# LMS7002M_Power.net
KiCad netlist of a schematic drawn in Altium Designer
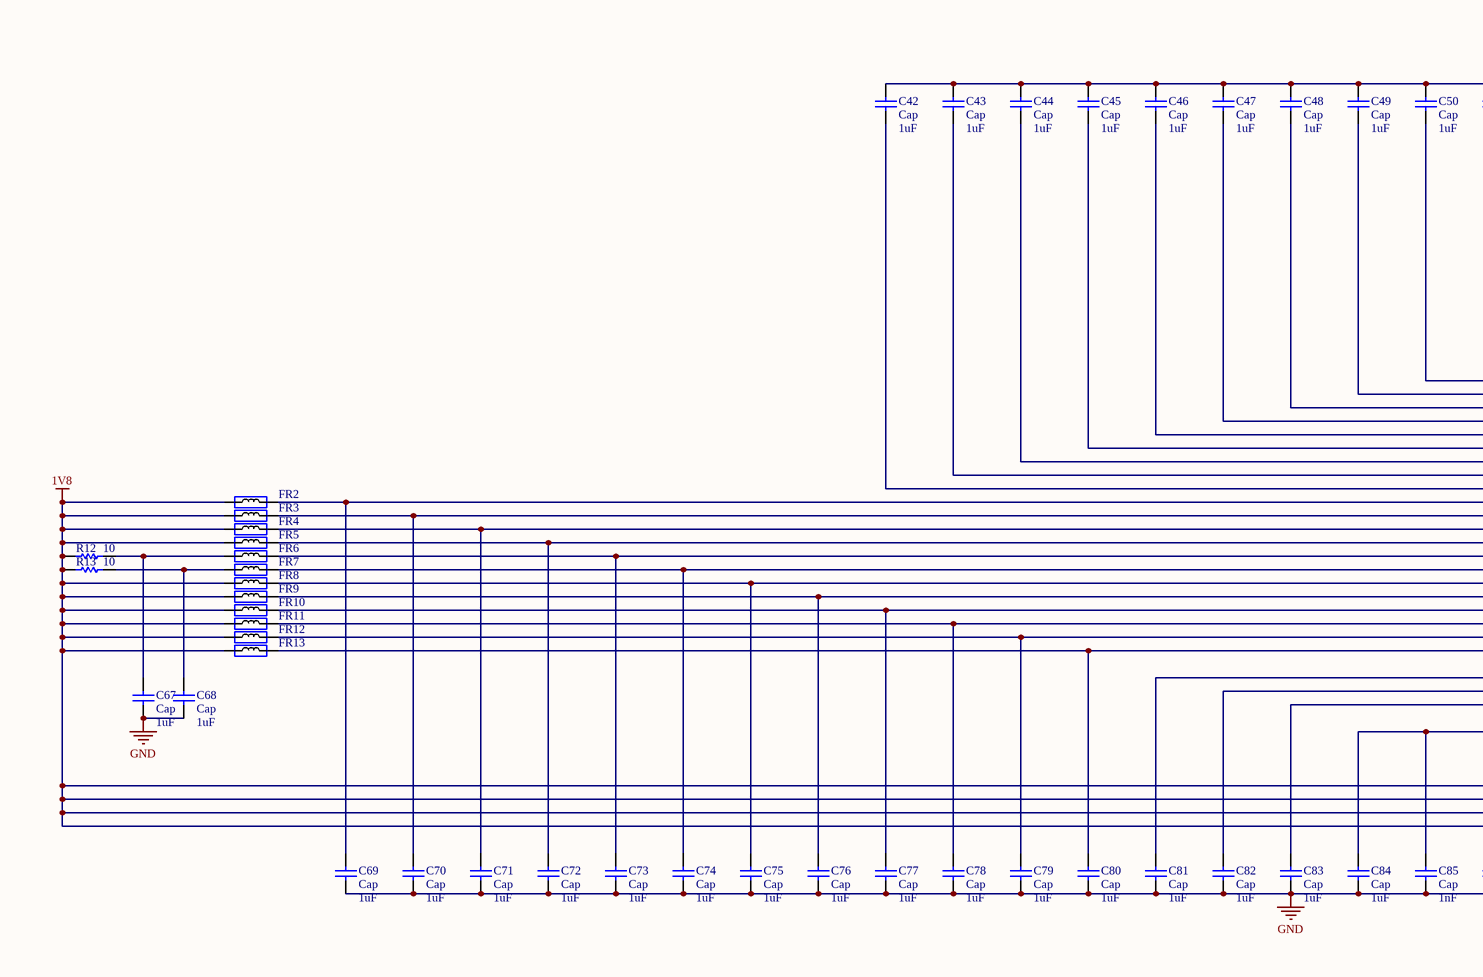
[diagram p0: LMS7002M Power.SchDoc, left]
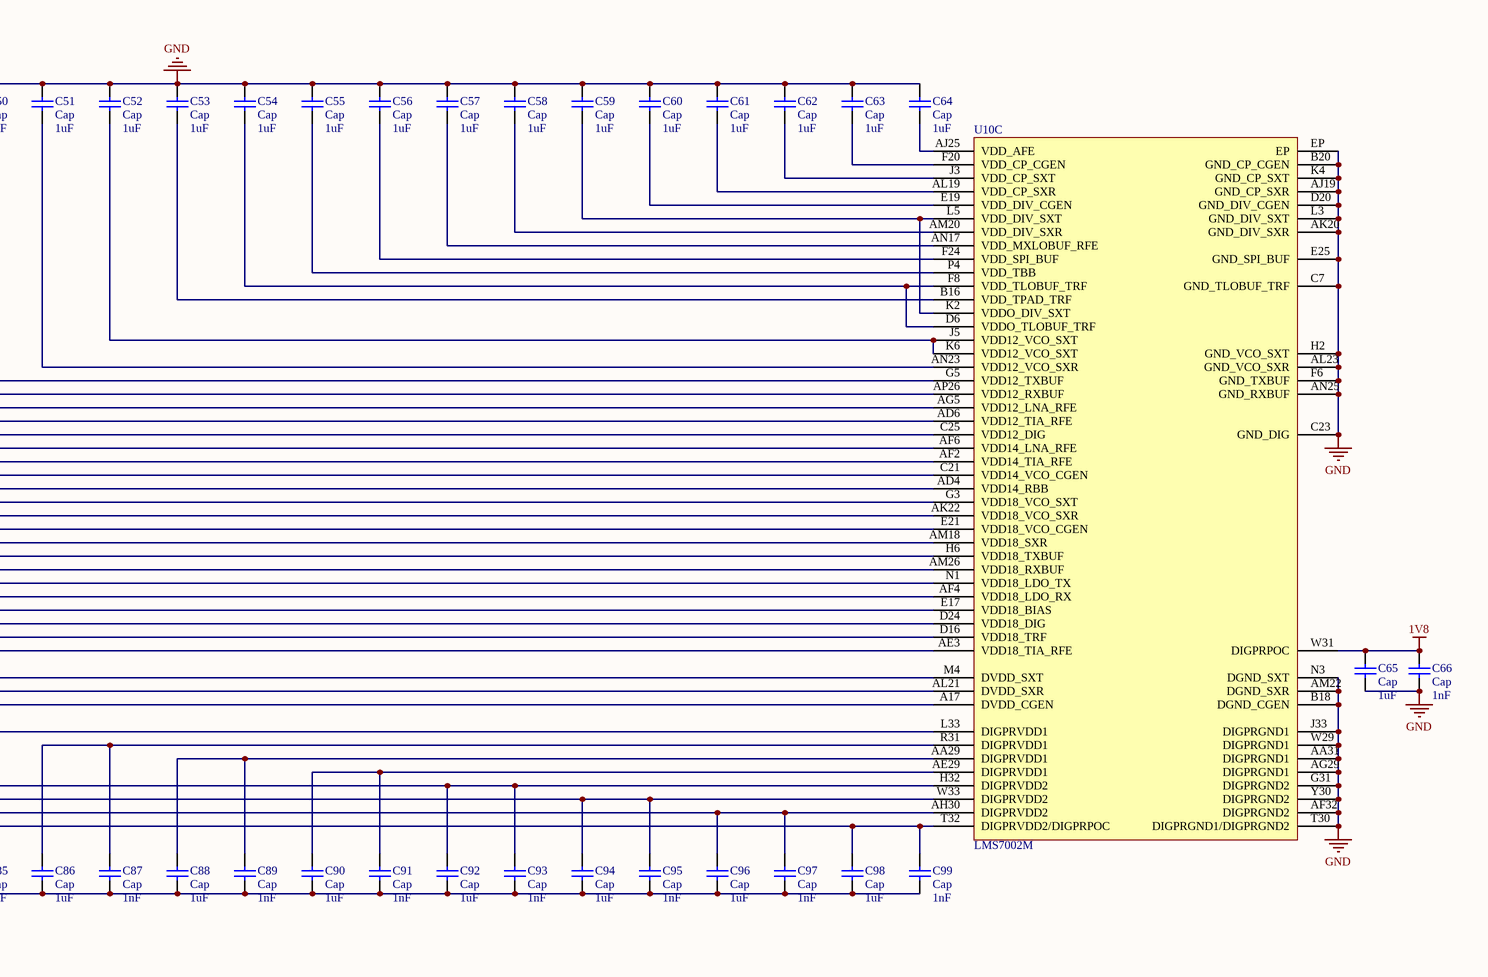
[diagram p1: LMS7002M Power.SchDoc, right]

(export (version "E")
  (design (tool "Eeschema 10.0.6"))
  (components
    (comp (ref "C42")
      (value "Cap")
      (footprint "0603")
      (description "Capacitor")
      (fields (field (name "ALTIUM_VALUE") "1uF") (field (name "PUBLISHER") "Altium Limited"))
      (libsource (lib "Miscellaneous Devices") (part "Cap"))
    )
    (comp (ref "C43")
      (value "Cap")
      (footprint "0603")
      (description "Capacitor")
      (fields (field (name "ALTIUM_VALUE") "1uF") (field (name "PUBLISHER") "Altium Limited"))
      (libsource (lib "Miscellaneous Devices") (part "Cap"))
    )
    (comp (ref "C44")
      (value "Cap")
      (footprint "0603")
      (description "Capacitor")
      (fields (field (name "ALTIUM_VALUE") "1uF") (field (name "PUBLISHER") "Altium Limited"))
      (libsource (lib "Miscellaneous Devices") (part "Cap"))
    )
    (comp (ref "C45")
      (value "Cap")
      (footprint "0603")
      (description "Capacitor")
      (fields (field (name "ALTIUM_VALUE") "1uF") (field (name "PUBLISHER") "Altium Limited"))
      (libsource (lib "Miscellaneous Devices") (part "Cap"))
    )
    (comp (ref "C46")
      (value "Cap")
      (footprint "0603")
      (description "Capacitor")
      (fields (field (name "ALTIUM_VALUE") "1uF") (field (name "PUBLISHER") "Altium Limited"))
      (libsource (lib "Miscellaneous Devices") (part "Cap"))
    )
    (comp (ref "C47")
      (value "Cap")
      (footprint "0603")
      (description "Capacitor")
      (fields (field (name "ALTIUM_VALUE") "1uF") (field (name "PUBLISHER") "Altium Limited"))
      (libsource (lib "Miscellaneous Devices") (part "Cap"))
    )
    (comp (ref "C48")
      (value "Cap")
      (footprint "0603")
      (description "Capacitor")
      (fields (field (name "ALTIUM_VALUE") "1uF") (field (name "PUBLISHER") "Altium Limited"))
      (libsource (lib "Miscellaneous Devices") (part "Cap"))
    )
    (comp (ref "C49")
      (value "Cap")
      (footprint "0603")
      (description "Capacitor")
      (fields (field (name "ALTIUM_VALUE") "1uF") (field (name "PUBLISHER") "Altium Limited"))
      (libsource (lib "Miscellaneous Devices") (part "Cap"))
    )
    (comp (ref "C50")
      (value "Cap")
      (footprint "0603")
      (description "Capacitor")
      (fields (field (name "ALTIUM_VALUE") "1uF") (field (name "PUBLISHER") "Altium Limited"))
      (libsource (lib "Miscellaneous Devices") (part "Cap"))
    )
    (comp (ref "C51")
      (value "Cap")
      (footprint "0603")
      (description "Capacitor")
      (fields (field (name "ALTIUM_VALUE") "1uF") (field (name "PUBLISHER") "Altium Limited"))
      (libsource (lib "Miscellaneous Devices") (part "Cap"))
    )
    (comp (ref "C52")
      (value "Cap")
      (footprint "0603")
      (description "Capacitor")
      (fields (field (name "ALTIUM_VALUE") "1uF") (field (name "PUBLISHER") "Altium Limited"))
      (libsource (lib "Miscellaneous Devices") (part "Cap"))
    )
    (comp (ref "C53")
      (value "Cap")
      (footprint "0603")
      (description "Capacitor")
      (fields (field (name "ALTIUM_VALUE") "1uF") (field (name "PUBLISHER") "Altium Limited"))
      (libsource (lib "Miscellaneous Devices") (part "Cap"))
    )
    (comp (ref "C54")
      (value "Cap")
      (footprint "0603")
      (description "Capacitor")
      (fields (field (name "ALTIUM_VALUE") "1uF") (field (name "PUBLISHER") "Altium Limited"))
      (libsource (lib "Miscellaneous Devices") (part "Cap"))
    )
    (comp (ref "C55")
      (value "Cap")
      (footprint "0603")
      (description "Capacitor")
      (fields (field (name "ALTIUM_VALUE") "1uF") (field (name "PUBLISHER") "Altium Limited"))
      (libsource (lib "Miscellaneous Devices") (part "Cap"))
    )
    (comp (ref "C56")
      (value "Cap")
      (footprint "0603")
      (description "Capacitor")
      (fields (field (name "ALTIUM_VALUE") "1uF") (field (name "PUBLISHER") "Altium Limited"))
      (libsource (lib "Miscellaneous Devices") (part "Cap"))
    )
    (comp (ref "C57")
      (value "Cap")
      (footprint "0603")
      (description "Capacitor")
      (fields (field (name "ALTIUM_VALUE") "1uF") (field (name "PUBLISHER") "Altium Limited"))
      (libsource (lib "Miscellaneous Devices") (part "Cap"))
    )
    (comp (ref "C58")
      (value "Cap")
      (footprint "0603")
      (description "Capacitor")
      (fields (field (name "ALTIUM_VALUE") "1uF") (field (name "PUBLISHER") "Altium Limited"))
      (libsource (lib "Miscellaneous Devices") (part "Cap"))
    )
    (comp (ref "C59")
      (value "Cap")
      (footprint "0603")
      (description "Capacitor")
      (fields (field (name "ALTIUM_VALUE") "1uF") (field (name "PUBLISHER") "Altium Limited"))
      (libsource (lib "Miscellaneous Devices") (part "Cap"))
    )
    (comp (ref "C60")
      (value "Cap")
      (footprint "0603")
      (description "Capacitor")
      (fields (field (name "ALTIUM_VALUE") "1uF") (field (name "PUBLISHER") "Altium Limited"))
      (libsource (lib "Miscellaneous Devices") (part "Cap"))
    )
    (comp (ref "C61")
      (value "Cap")
      (footprint "0603")
      (description "Capacitor")
      (fields (field (name "ALTIUM_VALUE") "1uF") (field (name "PUBLISHER") "Altium Limited"))
      (libsource (lib "Miscellaneous Devices") (part "Cap"))
    )
    (comp (ref "C62")
      (value "Cap")
      (footprint "0603")
      (description "Capacitor")
      (fields (field (name "ALTIUM_VALUE") "1uF") (field (name "PUBLISHER") "Altium Limited"))
      (libsource (lib "Miscellaneous Devices") (part "Cap"))
    )
    (comp (ref "C63")
      (value "Cap")
      (footprint "0603")
      (description "Capacitor")
      (fields (field (name "ALTIUM_VALUE") "1uF") (field (name "PUBLISHER") "Altium Limited"))
      (libsource (lib "Miscellaneous Devices") (part "Cap"))
    )
    (comp (ref "C64")
      (value "Cap")
      (footprint "0603")
      (description "Capacitor")
      (fields (field (name "ALTIUM_VALUE") "1uF") (field (name "PUBLISHER") "Altium Limited"))
      (libsource (lib "Miscellaneous Devices") (part "Cap"))
    )
    (comp (ref "C65")
      (value "Cap")
      (footprint "0603")
      (description "Capacitor")
      (fields (field (name "ALTIUM_VALUE") "1uF") (field (name "PUBLISHER") "Altium Limited"))
      (libsource (lib "Miscellaneous Devices") (part "Cap"))
    )
    (comp (ref "C66")
      (value "Cap")
      (footprint "0603")
      (description "Capacitor")
      (fields (field (name "ALTIUM_VALUE") "1nF") (field (name "PUBLISHER") "Altium Limited"))
      (libsource (lib "Miscellaneous Devices") (part "Cap"))
    )
    (comp (ref "C67")
      (value "Cap")
      (footprint "0603")
      (description "Capacitor")
      (fields (field (name "ALTIUM_VALUE") "1uF") (field (name "PUBLISHER") "Altium Limited"))
      (libsource (lib "Miscellaneous Devices") (part "Cap"))
    )
    (comp (ref "C68")
      (value "Cap")
      (footprint "0603")
      (description "Capacitor")
      (fields (field (name "ALTIUM_VALUE") "1uF") (field (name "PUBLISHER") "Altium Limited"))
      (libsource (lib "Miscellaneous Devices") (part "Cap"))
    )
    (comp (ref "C69")
      (value "Cap")
      (footprint "0603")
      (description "Capacitor")
      (fields (field (name "ALTIUM_VALUE") "1uF") (field (name "PUBLISHER") "Altium Limited"))
      (libsource (lib "Miscellaneous Devices") (part "Cap"))
    )
    (comp (ref "C70")
      (value "Cap")
      (footprint "0603")
      (description "Capacitor")
      (fields (field (name "ALTIUM_VALUE") "1uF") (field (name "PUBLISHER") "Altium Limited"))
      (libsource (lib "Miscellaneous Devices") (part "Cap"))
    )
    (comp (ref "C71")
      (value "Cap")
      (footprint "0603")
      (description "Capacitor")
      (fields (field (name "ALTIUM_VALUE") "1uF") (field (name "PUBLISHER") "Altium Limited"))
      (libsource (lib "Miscellaneous Devices") (part "Cap"))
    )
    (comp (ref "C72")
      (value "Cap")
      (footprint "0603")
      (description "Capacitor")
      (fields (field (name "ALTIUM_VALUE") "1uF") (field (name "PUBLISHER") "Altium Limited"))
      (libsource (lib "Miscellaneous Devices") (part "Cap"))
    )
    (comp (ref "C73")
      (value "Cap")
      (footprint "0603")
      (description "Capacitor")
      (fields (field (name "ALTIUM_VALUE") "1uF") (field (name "PUBLISHER") "Altium Limited"))
      (libsource (lib "Miscellaneous Devices") (part "Cap"))
    )
    (comp (ref "C74")
      (value "Cap")
      (footprint "0603")
      (description "Capacitor")
      (fields (field (name "ALTIUM_VALUE") "1uF") (field (name "PUBLISHER") "Altium Limited"))
      (libsource (lib "Miscellaneous Devices") (part "Cap"))
    )
    (comp (ref "C75")
      (value "Cap")
      (footprint "0603")
      (description "Capacitor")
      (fields (field (name "ALTIUM_VALUE") "1uF") (field (name "PUBLISHER") "Altium Limited"))
      (libsource (lib "Miscellaneous Devices") (part "Cap"))
    )
    (comp (ref "C76")
      (value "Cap")
      (footprint "0603")
      (description "Capacitor")
      (fields (field (name "ALTIUM_VALUE") "1uF") (field (name "PUBLISHER") "Altium Limited"))
      (libsource (lib "Miscellaneous Devices") (part "Cap"))
    )
    (comp (ref "C77")
      (value "Cap")
      (footprint "0603")
      (description "Capacitor")
      (fields (field (name "ALTIUM_VALUE") "1uF") (field (name "PUBLISHER") "Altium Limited"))
      (libsource (lib "Miscellaneous Devices") (part "Cap"))
    )
    (comp (ref "C78")
      (value "Cap")
      (footprint "0603")
      (description "Capacitor")
      (fields (field (name "ALTIUM_VALUE") "1uF") (field (name "PUBLISHER") "Altium Limited"))
      (libsource (lib "Miscellaneous Devices") (part "Cap"))
    )
    (comp (ref "C79")
      (value "Cap")
      (footprint "0603")
      (description "Capacitor")
      (fields (field (name "ALTIUM_VALUE") "1uF") (field (name "PUBLISHER") "Altium Limited"))
      (libsource (lib "Miscellaneous Devices") (part "Cap"))
    )
    (comp (ref "C80")
      (value "Cap")
      (footprint "0603")
      (description "Capacitor")
      (fields (field (name "ALTIUM_VALUE") "1uF") (field (name "PUBLISHER") "Altium Limited"))
      (libsource (lib "Miscellaneous Devices") (part "Cap"))
    )
    (comp (ref "C81")
      (value "Cap")
      (footprint "0603")
      (description "Capacitor")
      (fields (field (name "ALTIUM_VALUE") "1uF") (field (name "PUBLISHER") "Altium Limited"))
      (libsource (lib "Miscellaneous Devices") (part "Cap"))
    )
    (comp (ref "C82")
      (value "Cap")
      (footprint "0603")
      (description "Capacitor")
      (fields (field (name "ALTIUM_VALUE") "1uF") (field (name "PUBLISHER") "Altium Limited"))
      (libsource (lib "Miscellaneous Devices") (part "Cap"))
    )
    (comp (ref "C83")
      (value "Cap")
      (footprint "0603")
      (description "Capacitor")
      (fields (field (name "ALTIUM_VALUE") "1uF") (field (name "PUBLISHER") "Altium Limited"))
      (libsource (lib "Miscellaneous Devices") (part "Cap"))
    )
    (comp (ref "C84")
      (value "Cap")
      (footprint "0603")
      (description "Capacitor")
      (fields (field (name "ALTIUM_VALUE") "1uF") (field (name "PUBLISHER") "Altium Limited"))
      (libsource (lib "Miscellaneous Devices") (part "Cap"))
    )
    (comp (ref "C85")
      (value "Cap")
      (footprint "0603")
      (description "Capacitor")
      (fields (field (name "ALTIUM_VALUE") "1nF") (field (name "PUBLISHER") "Altium Limited"))
      (libsource (lib "Miscellaneous Devices") (part "Cap"))
    )
    (comp (ref "C86")
      (value "Cap")
      (footprint "0603")
      (description "Capacitor")
      (fields (field (name "ALTIUM_VALUE") "1uF") (field (name "PUBLISHER") "Altium Limited"))
      (libsource (lib "Miscellaneous Devices") (part "Cap"))
    )
    (comp (ref "C87")
      (value "Cap")
      (footprint "0603")
      (description "Capacitor")
      (fields (field (name "ALTIUM_VALUE") "1nF") (field (name "PUBLISHER") "Altium Limited"))
      (libsource (lib "Miscellaneous Devices") (part "Cap"))
    )
    (comp (ref "C88")
      (value "Cap")
      (footprint "0603")
      (description "Capacitor")
      (fields (field (name "ALTIUM_VALUE") "1uF") (field (name "PUBLISHER") "Altium Limited"))
      (libsource (lib "Miscellaneous Devices") (part "Cap"))
    )
    (comp (ref "C89")
      (value "Cap")
      (footprint "0603")
      (description "Capacitor")
      (fields (field (name "ALTIUM_VALUE") "1nF") (field (name "PUBLISHER") "Altium Limited"))
      (libsource (lib "Miscellaneous Devices") (part "Cap"))
    )
    (comp (ref "C90")
      (value "Cap")
      (footprint "0603")
      (description "Capacitor")
      (fields (field (name "ALTIUM_VALUE") "1uF") (field (name "PUBLISHER") "Altium Limited"))
      (libsource (lib "Miscellaneous Devices") (part "Cap"))
    )
    (comp (ref "C91")
      (value "Cap")
      (footprint "0603")
      (description "Capacitor")
      (fields (field (name "ALTIUM_VALUE") "1nF") (field (name "PUBLISHER") "Altium Limited"))
      (libsource (lib "Miscellaneous Devices") (part "Cap"))
    )
    (comp (ref "C92")
      (value "Cap")
      (footprint "0603")
      (description "Capacitor")
      (fields (field (name "ALTIUM_VALUE") "1uF") (field (name "PUBLISHER") "Altium Limited"))
      (libsource (lib "Miscellaneous Devices") (part "Cap"))
    )
    (comp (ref "C93")
      (value "Cap")
      (footprint "0603")
      (description "Capacitor")
      (fields (field (name "ALTIUM_VALUE") "1nF") (field (name "PUBLISHER") "Altium Limited"))
      (libsource (lib "Miscellaneous Devices") (part "Cap"))
    )
    (comp (ref "C94")
      (value "Cap")
      (footprint "0603")
      (description "Capacitor")
      (fields (field (name "ALTIUM_VALUE") "1uF") (field (name "PUBLISHER") "Altium Limited"))
      (libsource (lib "Miscellaneous Devices") (part "Cap"))
    )
    (comp (ref "C95")
      (value "Cap")
      (footprint "0603")
      (description "Capacitor")
      (fields (field (name "ALTIUM_VALUE") "1nF") (field (name "PUBLISHER") "Altium Limited"))
      (libsource (lib "Miscellaneous Devices") (part "Cap"))
    )
    (comp (ref "C96")
      (value "Cap")
      (footprint "0603")
      (description "Capacitor")
      (fields (field (name "ALTIUM_VALUE") "1uF") (field (name "PUBLISHER") "Altium Limited"))
      (libsource (lib "Miscellaneous Devices") (part "Cap"))
    )
    (comp (ref "C97")
      (value "Cap")
      (footprint "0603")
      (description "Capacitor")
      (fields (field (name "ALTIUM_VALUE") "1nF") (field (name "PUBLISHER") "Altium Limited"))
      (libsource (lib "Miscellaneous Devices") (part "Cap"))
    )
    (comp (ref "C98")
      (value "Cap")
      (footprint "0603")
      (description "Capacitor")
      (fields (field (name "ALTIUM_VALUE") "1uF") (field (name "PUBLISHER") "Altium Limited"))
      (libsource (lib "Miscellaneous Devices") (part "Cap"))
    )
    (comp (ref "C99")
      (value "Cap")
      (footprint "0603")
      (description "Capacitor")
      (fields (field (name "ALTIUM_VALUE") "1nF") (field (name "PUBLISHER") "Altium Limited"))
      (libsource (lib "Miscellaneous Devices") (part "Cap"))
    )
    (comp (ref "FR2")
      (value "600R, 0.27A")
      (footprint "0603")
      (fields (field (name "MANUFACTURER") "Taiyo Yuden"))
      (libsource (lib "LimeMicroAltiumLib_schLib") (part "Ferrite"))
    )
    (comp (ref "FR3")
      (value "600R, 0.27A")
      (footprint "0603")
      (fields (field (name "MANUFACTURER") "Taiyo Yuden"))
      (libsource (lib "LimeMicroAltiumLib_schLib") (part "Ferrite"))
    )
    (comp (ref "FR4")
      (value "600R, 0.27A")
      (footprint "0603")
      (fields (field (name "MANUFACTURER") "Taiyo Yuden"))
      (libsource (lib "LimeMicroAltiumLib_schLib") (part "Ferrite"))
    )
    (comp (ref "FR5")
      (value "600R, 0.27A")
      (footprint "0603")
      (fields (field (name "MANUFACTURER") "Taiyo Yuden"))
      (libsource (lib "LimeMicroAltiumLib_schLib") (part "Ferrite"))
    )
    (comp (ref "FR6")
      (value "600R, 0.27A")
      (footprint "0603")
      (fields (field (name "MANUFACTURER") "Taiyo Yuden"))
      (libsource (lib "LimeMicroAltiumLib_schLib") (part "Ferrite"))
    )
    (comp (ref "FR7")
      (value "600R, 0.27A")
      (footprint "0603")
      (fields (field (name "MANUFACTURER") "Taiyo Yuden"))
      (libsource (lib "LimeMicroAltiumLib_schLib") (part "Ferrite"))
    )
    (comp (ref "FR8")
      (value "600R, 0.27A")
      (footprint "0603")
      (fields (field (name "MANUFACTURER") "Taiyo Yuden"))
      (libsource (lib "LimeMicroAltiumLib_schLib") (part "Ferrite"))
    )
    (comp (ref "FR9")
      (value "600R, 0.27A")
      (footprint "0603")
      (fields (field (name "MANUFACTURER") "Taiyo Yuden"))
      (libsource (lib "LimeMicroAltiumLib_schLib") (part "Ferrite"))
    )
    (comp (ref "FR10")
      (value "600R, 0.27A")
      (footprint "0603")
      (fields (field (name "MANUFACTURER") "Taiyo Yuden"))
      (libsource (lib "LimeMicroAltiumLib_schLib") (part "Ferrite"))
    )
    (comp (ref "FR11")
      (value "600R, 0.27A")
      (footprint "0603")
      (fields (field (name "MANUFACTURER") "Taiyo Yuden"))
      (libsource (lib "LimeMicroAltiumLib_schLib") (part "Ferrite"))
    )
    (comp (ref "FR12")
      (value "600R, 0.27A")
      (footprint "0603")
      (fields (field (name "MANUFACTURER") "Taiyo Yuden"))
      (libsource (lib "LimeMicroAltiumLib_schLib") (part "Ferrite"))
    )
    (comp (ref "FR13")
      (value "600R, 0.27A")
      (footprint "0603")
      (fields (field (name "MANUFACTURER") "Taiyo Yuden"))
      (libsource (lib "LimeMicroAltiumLib_schLib") (part "Ferrite"))
    )
    (comp (ref "R12")
      (value "10")
      (footprint "0402-A")
      (description "Resistor")
      (fields (field (name "Comment") "Res1") (field (name "PUBLISHER") "Altium Limited"))
      (libsource (lib "Miscellaneous Devices") (part "Res1"))
    )
    (comp (ref "R13")
      (value "10")
      (footprint "0402-A")
      (description "Resistor")
      (fields (field (name "Comment") "Res1") (field (name "PUBLISHER") "Altium Limited"))
      (libsource (lib "Miscellaneous Devices") (part "Res1"))
    )
    (comp (ref "U10")
      (value "LMS7002M")
      (footprint "LM-QFN-261_V")
      (fields (field (name "MANUFACTURER") "LimeMicrosystemsLtd"))
      (libsource (lib "Altium Content Vault") (part "LM-LMS7002M-QFN-261"))
    )
  )
  (nets
    (net (code "1") (name "1V8") (class "Default")
      (node (ref "C65") (pin "2") (pinfunction "2_2") (pintype "passive"))
      (node (ref "C66") (pin "2") (pinfunction "2_2") (pintype "passive"))
      (node (ref "C92") (pin "2") (pinfunction "2_2") (pintype "passive"))
      (node (ref "C93") (pin "2") (pinfunction "2_2") (pintype "passive"))
      (node (ref "C94") (pin "2") (pinfunction "2_2") (pintype "passive"))
      (node (ref "C95") (pin "2") (pinfunction "2_2") (pintype "passive"))
      (node (ref "C96") (pin "2") (pinfunction "2_2") (pintype "passive"))
      (node (ref "C97") (pin "2") (pinfunction "2_2") (pintype "passive"))
      (node (ref "C98") (pin "2") (pinfunction "2_2") (pintype "passive"))
      (node (ref "C99") (pin "2") (pinfunction "2_2") (pintype "passive"))
      (node (ref "FR10") (pin "1") (pinfunction "1_1") (pintype "passive"))
      (node (ref "FR11") (pin "1") (pinfunction "1_1") (pintype "passive"))
      (node (ref "FR12") (pin "1") (pinfunction "1_1") (pintype "passive"))
      (node (ref "FR13") (pin "1") (pinfunction "1_1") (pintype "passive"))
      (node (ref "FR2") (pin "1") (pinfunction "1_1") (pintype "passive"))
      (node (ref "FR3") (pin "1") (pinfunction "1_1") (pintype "passive"))
      (node (ref "FR4") (pin "1") (pinfunction "1_1") (pintype "passive"))
      (node (ref "FR5") (pin "1") (pinfunction "1_1") (pintype "passive"))
      (node (ref "FR8") (pin "1") (pinfunction "1_1") (pintype "passive"))
      (node (ref "FR9") (pin "1") (pinfunction "1_1") (pintype "passive"))
      (node (ref "R12") (pin "1") (pinfunction "1_1") (pintype "passive"))
      (node (ref "R13") (pin "1") (pinfunction "1_1") (pintype "passive"))
      (node (ref "U10") (pin "AH30") (pinfunction "DIGPRVDD2_AH30") (pintype "power_in"))
      (node (ref "U10") (pin "H32") (pinfunction "DIGPRVDD2_H32") (pintype "power_in"))
      (node (ref "U10") (pin "T32") (pinfunction "DIGPRVDD2/DIGPRPOC_T32") (pintype "power_in"))
      (node (ref "U10") (pin "W31") (pinfunction "DIGPRPOC_W31") (pintype "passive"))
      (node (ref "U10") (pin "W33") (pinfunction "DIGPRVDD2_W33") (pintype "power_in"))
    )
    (net (code "2") (name "GND") (class "Default")
      (node (ref "C42") (pin "2") (pinfunction "2_2") (pintype "passive"))
      (node (ref "C43") (pin "2") (pinfunction "2_2") (pintype "passive"))
      (node (ref "C44") (pin "2") (pinfunction "2_2") (pintype "passive"))
      (node (ref "C45") (pin "2") (pinfunction "2_2") (pintype "passive"))
      (node (ref "C46") (pin "2") (pinfunction "2_2") (pintype "passive"))
      (node (ref "C47") (pin "2") (pinfunction "2_2") (pintype "passive"))
      (node (ref "C48") (pin "2") (pinfunction "2_2") (pintype "passive"))
      (node (ref "C49") (pin "2") (pinfunction "2_2") (pintype "passive"))
      (node (ref "C50") (pin "2") (pinfunction "2_2") (pintype "passive"))
      (node (ref "C51") (pin "2") (pinfunction "2_2") (pintype "passive"))
      (node (ref "C52") (pin "2") (pinfunction "2_2") (pintype "passive"))
      (node (ref "C53") (pin "2") (pinfunction "2_2") (pintype "passive"))
      (node (ref "C54") (pin "2") (pinfunction "2_2") (pintype "passive"))
      (node (ref "C55") (pin "2") (pinfunction "2_2") (pintype "passive"))
      (node (ref "C56") (pin "2") (pinfunction "2_2") (pintype "passive"))
      (node (ref "C57") (pin "2") (pinfunction "2_2") (pintype "passive"))
      (node (ref "C58") (pin "2") (pinfunction "2_2") (pintype "passive"))
      (node (ref "C59") (pin "2") (pinfunction "2_2") (pintype "passive"))
      (node (ref "C60") (pin "2") (pinfunction "2_2") (pintype "passive"))
      (node (ref "C61") (pin "2") (pinfunction "2_2") (pintype "passive"))
      (node (ref "C62") (pin "2") (pinfunction "2_2") (pintype "passive"))
      (node (ref "C63") (pin "2") (pinfunction "2_2") (pintype "passive"))
      (node (ref "C64") (pin "2") (pinfunction "2_2") (pintype "passive"))
      (node (ref "C65") (pin "1") (pinfunction "1_1") (pintype "passive"))
      (node (ref "C66") (pin "1") (pinfunction "1_1") (pintype "passive"))
      (node (ref "C67") (pin "1") (pinfunction "1_1") (pintype "passive"))
      (node (ref "C68") (pin "1") (pinfunction "1_1") (pintype "passive"))
      (node (ref "C69") (pin "1") (pinfunction "1_1") (pintype "passive"))
      (node (ref "C70") (pin "1") (pinfunction "1_1") (pintype "passive"))
      (node (ref "C71") (pin "1") (pinfunction "1_1") (pintype "passive"))
      (node (ref "C72") (pin "1") (pinfunction "1_1") (pintype "passive"))
      (node (ref "C73") (pin "1") (pinfunction "1_1") (pintype "passive"))
      (node (ref "C74") (pin "1") (pinfunction "1_1") (pintype "passive"))
      (node (ref "C75") (pin "1") (pinfunction "1_1") (pintype "passive"))
      (node (ref "C76") (pin "1") (pinfunction "1_1") (pintype "passive"))
      (node (ref "C77") (pin "1") (pinfunction "1_1") (pintype "passive"))
      (node (ref "C78") (pin "1") (pinfunction "1_1") (pintype "passive"))
      (node (ref "C79") (pin "1") (pinfunction "1_1") (pintype "passive"))
      (node (ref "C80") (pin "1") (pinfunction "1_1") (pintype "passive"))
      (node (ref "C81") (pin "1") (pinfunction "1_1") (pintype "passive"))
      (node (ref "C82") (pin "1") (pinfunction "1_1") (pintype "passive"))
      (node (ref "C83") (pin "1") (pinfunction "1_1") (pintype "passive"))
      (node (ref "C84") (pin "1") (pinfunction "1_1") (pintype "passive"))
      (node (ref "C85") (pin "1") (pinfunction "1_1") (pintype "passive"))
      (node (ref "C86") (pin "1") (pinfunction "1_1") (pintype "passive"))
      (node (ref "C87") (pin "1") (pinfunction "1_1") (pintype "passive"))
      (node (ref "C88") (pin "1") (pinfunction "1_1") (pintype "passive"))
      (node (ref "C89") (pin "1") (pinfunction "1_1") (pintype "passive"))
      (node (ref "C90") (pin "1") (pinfunction "1_1") (pintype "passive"))
      (node (ref "C91") (pin "1") (pinfunction "1_1") (pintype "passive"))
      (node (ref "C92") (pin "1") (pinfunction "1_1") (pintype "passive"))
      (node (ref "C93") (pin "1") (pinfunction "1_1") (pintype "passive"))
      (node (ref "C94") (pin "1") (pinfunction "1_1") (pintype "passive"))
      (node (ref "C95") (pin "1") (pinfunction "1_1") (pintype "passive"))
      (node (ref "C96") (pin "1") (pinfunction "1_1") (pintype "passive"))
      (node (ref "C97") (pin "1") (pinfunction "1_1") (pintype "passive"))
      (node (ref "C98") (pin "1") (pinfunction "1_1") (pintype "passive"))
      (node (ref "C99") (pin "1") (pinfunction "1_1") (pintype "passive"))
      (node (ref "U10") (pin "AA31") (pinfunction "DIGPRGND1_AA31") (pintype "power_in"))
      (node (ref "U10") (pin "AF32") (pinfunction "DIGPRGND2_AF32") (pintype "power_in"))
      (node (ref "U10") (pin "AG29") (pinfunction "DIGPRGND1_AG29") (pintype "power_in"))
      (node (ref "U10") (pin "AJ19") (pinfunction "GND_CP_SXR_AJ19") (pintype "power_in"))
      (node (ref "U10") (pin "AK20") (pinfunction "GND_DIV_SXR_AK20") (pintype "power_in"))
      (node (ref "U10") (pin "AL23") (pinfunction "GND_VCO_SXR_AL23") (pintype "power_in"))
      (node (ref "U10") (pin "AM22") (pinfunction "DGND_SXR_AM22") (pintype "power_in"))
      (node (ref "U10") (pin "AN25") (pinfunction "GND_RXBUF_AN25") (pintype "power_in"))
      (node (ref "U10") (pin "B18") (pinfunction "DGND_CGEN_B18") (pintype "power_in"))
      (node (ref "U10") (pin "B20") (pinfunction "GND_CP_CGEN_B20") (pintype "power_in"))
      (node (ref "U10") (pin "C23") (pinfunction "GND_DIG_C23") (pintype "power_in"))
      (node (ref "U10") (pin "C7") (pinfunction "GND_TLOBUF_TRF_C7") (pintype "power_in"))
      (node (ref "U10") (pin "D20") (pinfunction "GND_DIV_CGEN_D20") (pintype "power_in"))
      (node (ref "U10") (pin "E25") (pinfunction "GND_SPI_BUF_E25") (pintype "power_in"))
      (node (ref "U10") (pin "EP") (pinfunction "EP_EP") (pintype "passive"))
      (node (ref "U10") (pin "F6") (pinfunction "GND_TXBUF_F6") (pintype "power_in"))
      (node (ref "U10") (pin "G31") (pinfunction "DIGPRGND2_G31") (pintype "power_in"))
      (node (ref "U10") (pin "H2") (pinfunction "GND_VCO_SXT_H2") (pintype "power_in"))
      (node (ref "U10") (pin "J33") (pinfunction "DIGPRGND1_J33") (pintype "power_in"))
      (node (ref "U10") (pin "K4") (pinfunction "GND_CP_SXT_K4") (pintype "power_in"))
      (node (ref "U10") (pin "L3") (pinfunction "GND_DIV_SXT_L3") (pintype "power_in"))
      (node (ref "U10") (pin "N3") (pinfunction "DGND_SXT_N3") (pintype "power_in"))
      (node (ref "U10") (pin "T30") (pinfunction "DIGPRGND1/DIGPRGND2_T30") (pintype "power_in"))
      (node (ref "U10") (pin "W29") (pinfunction "DIGPRGND1_W29") (pintype "power_in"))
      (node (ref "U10") (pin "Y30") (pinfunction "DIGPRGND2_Y30") (pintype "power_in"))
    )
    (net (code "3") (name "Net-(C52-Pad1)") (class "Default")
      (node (ref "C52") (pin "1") (pinfunction "1_1") (pintype "passive"))
      (node (ref "U10") (pin "J5") (pinfunction "VDD12_VCO_SXT_J5") (pintype "power_in"))
      (node (ref "U10") (pin "K6") (pinfunction "VDD12_VCO_SXT_K6") (pintype "power_in"))
    )
    (net (code "4") (name "Net-(C67-Pad2)") (class "Default")
      (node (ref "C67") (pin "2") (pinfunction "2_2") (pintype "passive"))
      (node (ref "FR6") (pin "1") (pinfunction "1_1") (pintype "passive"))
      (node (ref "R12") (pin "2") (pinfunction "2_2") (pintype "passive"))
    )
    (net (code "5") (name "Net-(C68-Pad2)") (class "Default")
      (node (ref "C68") (pin "2") (pinfunction "2_2") (pintype "passive"))
      (node (ref "FR7") (pin "1") (pinfunction "1_1") (pintype "passive"))
      (node (ref "R13") (pin "2") (pinfunction "2_2") (pintype "passive"))
    )
    (net (code "6") (name "Net-(C84-Pad2)") (class "Default")
      (node (ref "C84") (pin "2") (pinfunction "2_2") (pintype "passive"))
      (node (ref "C85") (pin "2") (pinfunction "2_2") (pintype "passive"))
      (node (ref "U10") (pin "L33") (pinfunction "DIGPRVDD1_L33") (pintype "power_in"))
    )
    (net (code "7") (name "Net-(C86-Pad2)") (class "Default")
      (node (ref "C86") (pin "2") (pinfunction "2_2") (pintype "passive"))
      (node (ref "C87") (pin "2") (pinfunction "2_2") (pintype "passive"))
      (node (ref "U10") (pin "R31") (pinfunction "DIGPRVDD1_R31") (pintype "power_in"))
    )
    (net (code "8") (name "Net-(C88-Pad2)") (class "Default")
      (node (ref "C88") (pin "2") (pinfunction "2_2") (pintype "passive"))
      (node (ref "C89") (pin "2") (pinfunction "2_2") (pintype "passive"))
      (node (ref "U10") (pin "AA29") (pinfunction "DIGPRVDD1_AA29") (pintype "power_in"))
    )
    (net (code "9") (name "Net-(C90-Pad2)") (class "Default")
      (node (ref "C90") (pin "2") (pinfunction "2_2") (pintype "passive"))
      (node (ref "C91") (pin "2") (pinfunction "2_2") (pintype "passive"))
      (node (ref "U10") (pin "AE29") (pinfunction "DIGPRVDD1_AE29") (pintype "power_in"))
    )
    (net (code "10") (name "Net-(U10C-DVDD_CGEN)") (class "Default")
      (node (ref "C83") (pin "2") (pinfunction "2_2") (pintype "passive"))
      (node (ref "U10") (pin "A17") (pinfunction "DVDD_CGEN_A17") (pintype "power_in"))
    )
    (net (code "11") (name "Net-(U10C-DVDD_SXR)") (class "Default")
      (node (ref "C82") (pin "2") (pinfunction "2_2") (pintype "passive"))
      (node (ref "U10") (pin "AL21") (pinfunction "DVDD_SXR_AL21") (pintype "power_in"))
    )
    (net (code "12") (name "Net-(U10C-DVDD_SXT)") (class "Default")
      (node (ref "C81") (pin "2") (pinfunction "2_2") (pintype "passive"))
      (node (ref "U10") (pin "M4") (pinfunction "DVDD_SXT_M4") (pintype "power_in"))
    )
    (net (code "13") (name "Net-(U10C-VDD12_DIG)") (class "Default")
      (node (ref "C46") (pin "1") (pinfunction "1_1") (pintype "passive"))
      (node (ref "U10") (pin "C25") (pinfunction "VDD12_DIG_C25") (pintype "power_in"))
    )
    (net (code "14") (name "Net-(U10C-VDD12_LNA_RFE)") (class "Default")
      (node (ref "C48") (pin "1") (pinfunction "1_1") (pintype "passive"))
      (node (ref "U10") (pin "AG5") (pinfunction "VDD12_LNA_RFE_AG5") (pintype "power_in"))
    )
    (net (code "15") (name "Net-(U10C-VDD12_RXBUF)") (class "Default")
      (node (ref "C49") (pin "1") (pinfunction "1_1") (pintype "passive"))
      (node (ref "U10") (pin "AP26") (pinfunction "VDD12_RXBUF_AP26") (pintype "power_in"))
    )
    (net (code "16") (name "Net-(U10C-VDD12_TIA_RFE)") (class "Default")
      (node (ref "C47") (pin "1") (pinfunction "1_1") (pintype "passive"))
      (node (ref "U10") (pin "AD6") (pinfunction "VDD12_TIA_RFE_AD6") (pintype "power_in"))
    )
    (net (code "17") (name "Net-(U10C-VDD12_TXBUF)") (class "Default")
      (node (ref "C50") (pin "1") (pinfunction "1_1") (pintype "passive"))
      (node (ref "U10") (pin "G5") (pinfunction "VDD12_TXBUF_G5") (pintype "power_in"))
    )
    (net (code "18") (name "Net-(U10C-VDD12_VCO_SXR)") (class "Default")
      (node (ref "C51") (pin "1") (pinfunction "1_1") (pintype "passive"))
      (node (ref "U10") (pin "AN23") (pinfunction "VDD12_VCO_SXR_AN23") (pintype "power_in"))
    )
    (net (code "19") (name "Net-(U10C-VDD14_LNA_RFE)") (class "Default")
      (node (ref "C45") (pin "1") (pinfunction "1_1") (pintype "passive"))
      (node (ref "U10") (pin "AF6") (pinfunction "VDD14_LNA_RFE_AF6") (pintype "power_in"))
    )
    (net (code "20") (name "Net-(U10C-VDD14_RBB)") (class "Default")
      (node (ref "C42") (pin "1") (pinfunction "1_1") (pintype "passive"))
      (node (ref "U10") (pin "AD4") (pinfunction "VDD14_RBB_AD4") (pintype "power_in"))
    )
    (net (code "21") (name "Net-(U10C-VDD14_TIA_RFE)") (class "Default")
      (node (ref "C44") (pin "1") (pinfunction "1_1") (pintype "passive"))
      (node (ref "U10") (pin "AF2") (pinfunction "VDD14_TIA_RFE_AF2") (pintype "power_in"))
    )
    (net (code "22") (name "Net-(U10C-VDD14_VCO_CGEN)") (class "Default")
      (node (ref "C43") (pin "1") (pinfunction "1_1") (pintype "passive"))
      (node (ref "U10") (pin "C21") (pinfunction "VDD14_VCO_CGEN_C21") (pintype "power_in"))
    )
    (net (code "23") (name "Net-(U10C-VDD18_BIAS)") (class "Default")
      (node (ref "C77") (pin "2") (pinfunction "2_2") (pintype "passive"))
      (node (ref "FR10") (pin "2") (pinfunction "2_2") (pintype "passive"))
      (node (ref "U10") (pin "E17") (pinfunction "VDD18_BIAS_E17") (pintype "power_in"))
    )
    (net (code "24") (name "Net-(U10C-VDD18_DIG)") (class "Default")
      (node (ref "C78") (pin "2") (pinfunction "2_2") (pintype "passive"))
      (node (ref "FR11") (pin "2") (pinfunction "2_2") (pintype "passive"))
      (node (ref "U10") (pin "D24") (pinfunction "VDD18_DIG_D24") (pintype "power_in"))
    )
    (net (code "25") (name "Net-(U10C-VDD18_LDO_RX)") (class "Default")
      (node (ref "C76") (pin "2") (pinfunction "2_2") (pintype "passive"))
      (node (ref "FR9") (pin "2") (pinfunction "2_2") (pintype "passive"))
      (node (ref "U10") (pin "AF4") (pinfunction "VDD18_LDO_RX_AF4") (pintype "power_in"))
    )
    (net (code "26") (name "Net-(U10C-VDD18_LDO_TX)") (class "Default")
      (node (ref "C75") (pin "2") (pinfunction "2_2") (pintype "passive"))
      (node (ref "FR8") (pin "2") (pinfunction "2_2") (pintype "passive"))
      (node (ref "U10") (pin "N1") (pinfunction "VDD18_LDO_TX_N1") (pintype "power_in"))
    )
    (net (code "27") (name "Net-(U10C-VDD18_RXBUF)") (class "Default")
      (node (ref "C74") (pin "2") (pinfunction "2_2") (pintype "passive"))
      (node (ref "FR7") (pin "2") (pinfunction "2_2") (pintype "passive"))
      (node (ref "U10") (pin "AM26") (pinfunction "VDD18_RXBUF_AM26") (pintype "power_in"))
    )
    (net (code "28") (name "Net-(U10C-VDD18_SXR)") (class "Default")
      (node (ref "C72") (pin "2") (pinfunction "2_2") (pintype "passive"))
      (node (ref "FR5") (pin "2") (pinfunction "2_2") (pintype "passive"))
      (node (ref "U10") (pin "AM18") (pinfunction "VDD18_SXR_AM18") (pintype "power_in"))
    )
    (net (code "29") (name "Net-(U10C-VDD18_TIA_RFE)") (class "Default")
      (node (ref "C80") (pin "2") (pinfunction "2_2") (pintype "passive"))
      (node (ref "FR13") (pin "2") (pinfunction "2_2") (pintype "passive"))
      (node (ref "U10") (pin "AE3") (pinfunction "VDD18_TIA_RFE_AE3") (pintype "power_in"))
    )
    (net (code "30") (name "Net-(U10C-VDD18_TRF)") (class "Default")
      (node (ref "C79") (pin "2") (pinfunction "2_2") (pintype "passive"))
      (node (ref "FR12") (pin "2") (pinfunction "2_2") (pintype "passive"))
      (node (ref "U10") (pin "D16") (pinfunction "VDD18_TRF_D16") (pintype "power_in"))
    )
    (net (code "31") (name "Net-(U10C-VDD18_TXBUF)") (class "Default")
      (node (ref "C73") (pin "2") (pinfunction "2_2") (pintype "passive"))
      (node (ref "FR6") (pin "2") (pinfunction "2_2") (pintype "passive"))
      (node (ref "U10") (pin "H6") (pinfunction "VDD18_TXBUF_H6") (pintype "power_in"))
    )
    (net (code "32") (name "Net-(U10C-VDD18_VCO_CGEN)") (class "Default")
      (node (ref "C71") (pin "2") (pinfunction "2_2") (pintype "passive"))
      (node (ref "FR4") (pin "2") (pinfunction "2_2") (pintype "passive"))
      (node (ref "U10") (pin "E21") (pinfunction "VDD18_VCO_CGEN_E21") (pintype "power_in"))
    )
    (net (code "33") (name "Net-(U10C-VDD18_VCO_SXR)") (class "Default")
      (node (ref "C70") (pin "2") (pinfunction "2_2") (pintype "passive"))
      (node (ref "FR3") (pin "2") (pinfunction "2_2") (pintype "passive"))
      (node (ref "U10") (pin "AK22") (pinfunction "VDD18_VCO_SXR_AK22") (pintype "power_in"))
    )
    (net (code "34") (name "Net-(U10C-VDD18_VCO_SXT)") (class "Default")
      (node (ref "C69") (pin "2") (pinfunction "2_2") (pintype "passive"))
      (node (ref "FR2") (pin "2") (pinfunction "2_2") (pintype "passive"))
      (node (ref "U10") (pin "G3") (pinfunction "VDD18_VCO_SXT_G3") (pintype "power_in"))
    )
    (net (code "35") (name "Net-(U10C-VDDO_DIV_SXT)") (class "Default")
      (node (ref "C59") (pin "1") (pinfunction "1_1") (pintype "passive"))
      (node (ref "U10") (pin "K2") (pinfunction "VDDO_DIV_SXT_K2") (pintype "power_in"))
      (node (ref "U10") (pin "L5") (pinfunction "VDD_DIV_SXT_L5") (pintype "power_in"))
    )
    (net (code "36") (name "Net-(U10C-VDDO_TLOBUF_TRF)") (class "Default")
      (node (ref "C54") (pin "1") (pinfunction "1_1") (pintype "passive"))
      (node (ref "U10") (pin "D6") (pinfunction "VDDO_TLOBUF_TRF_D6") (pintype "power_in"))
      (node (ref "U10") (pin "F8") (pinfunction "VDD_TLOBUF_TRF_F8") (pintype "power_in"))
    )
    (net (code "37") (name "Net-(U10C-VDD_AFE)") (class "Default")
      (node (ref "C64") (pin "1") (pinfunction "1_1") (pintype "passive"))
      (node (ref "U10") (pin "AJ25") (pinfunction "VDD_AFE_AJ25") (pintype "power_in"))
    )
    (net (code "38") (name "Net-(U10C-VDD_CP_CGEN)") (class "Default")
      (node (ref "C63") (pin "1") (pinfunction "1_1") (pintype "passive"))
      (node (ref "U10") (pin "F20") (pinfunction "VDD_CP_CGEN_F20") (pintype "power_in"))
    )
    (net (code "39") (name "Net-(U10C-VDD_CP_SXR)") (class "Default")
      (node (ref "C61") (pin "1") (pinfunction "1_1") (pintype "passive"))
      (node (ref "U10") (pin "AL19") (pinfunction "VDD_CP_SXR_AL19") (pintype "power_in"))
    )
    (net (code "40") (name "Net-(U10C-VDD_CP_SXT)") (class "Default")
      (node (ref "C62") (pin "1") (pinfunction "1_1") (pintype "passive"))
      (node (ref "U10") (pin "J3") (pinfunction "VDD_CP_SXT_J3") (pintype "power_in"))
    )
    (net (code "41") (name "Net-(U10C-VDD_DIV_CGEN)") (class "Default")
      (node (ref "C60") (pin "1") (pinfunction "1_1") (pintype "passive"))
      (node (ref "U10") (pin "E19") (pinfunction "VDD_DIV_CGEN_E19") (pintype "power_in"))
    )
    (net (code "42") (name "Net-(U10C-VDD_DIV_SXR)") (class "Default")
      (node (ref "C58") (pin "1") (pinfunction "1_1") (pintype "passive"))
      (node (ref "U10") (pin "AM20") (pinfunction "VDD_DIV_SXR_AM20") (pintype "power_in"))
    )
    (net (code "43") (name "Net-(U10C-VDD_MXLOBUF_RFE)") (class "Default")
      (node (ref "C57") (pin "1") (pinfunction "1_1") (pintype "passive"))
      (node (ref "U10") (pin "AN17") (pinfunction "VDD_MXLOBUF_RFE_AN17") (pintype "power_in"))
    )
    (net (code "44") (name "Net-(U10C-VDD_SPI_BUF)") (class "Default")
      (node (ref "C56") (pin "1") (pinfunction "1_1") (pintype "passive"))
      (node (ref "U10") (pin "F24") (pinfunction "VDD_SPI_BUF_F24") (pintype "power_in"))
    )
    (net (code "45") (name "Net-(U10C-VDD_TBB)") (class "Default")
      (node (ref "C55") (pin "1") (pinfunction "1_1") (pintype "passive"))
      (node (ref "U10") (pin "P4") (pinfunction "VDD_TBB_P4") (pintype "power_in"))
    )
    (net (code "46") (name "Net-(U10C-VDD_TPAD_TRF)") (class "Default")
      (node (ref "C53") (pin "1") (pinfunction "1_1") (pintype "passive"))
      (node (ref "U10") (pin "B16") (pinfunction "VDD_TPAD_TRF_B16") (pintype "power_in"))
    )
  )
)
